# 03-VS1053B.net
KiCad netlist of a schematic drawn in Altium Designer
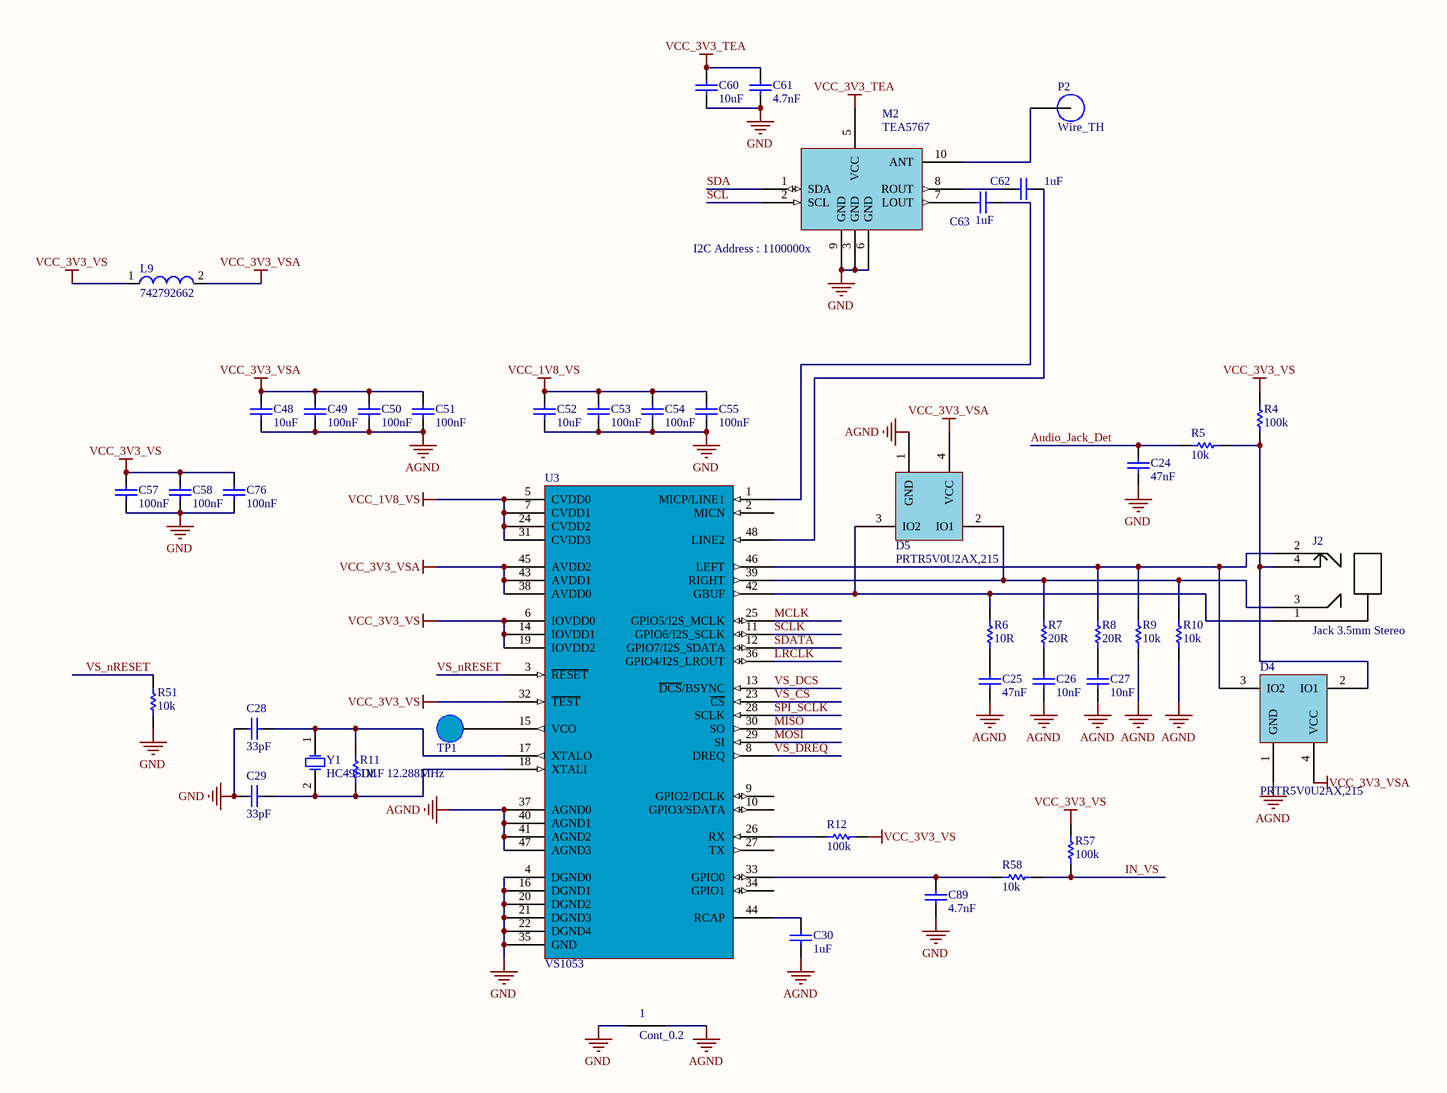
[diagram p0: 03-VS1053B.SchDoc]

(export (version "E")
  (design (tool "Eeschema 10.0.6"))
  (components
    (comp (ref "1")
      (value "Cont_0.2")
      (footprint "PcbLib:CONT_0.2")
      (description "Split Net Name 0.2mm")
      (libsource (lib "Connectors") (part "Cont_0.2"))
    )
    (comp (ref "C24")
      (value "47nF")
      (footprint "Aptustech:CAPC1608X06N")
      (description "47nF 50V 0603 X7R")
      (fields (field (name "VOLTAGE") "50V") (field (name "TOLERANCE") "10%"))
      (libsource (lib "Cap_0603") (part "47nF 50V 0603 X7R"))
    )
    (comp (ref "C25")
      (value "47nF")
      (footprint "Aptustech:CAPC1608X06N")
      (description "47nF 50V 0603 X7R")
      (fields (field (name "VOLTAGE") "50V") (field (name "TOLERANCE") "10%"))
      (libsource (lib "Cap_0603") (part "47nF 50V 0603 X7R"))
    )
    (comp (ref "C26")
      (value "10nF")
      (footprint "Aptustech:CAPC1608X06N")
      (description "10nF 50V 0603 NP0")
      (fields (field (name "VOLTAGE") "50V") (field (name "TOLERANCE") "10%"))
      (libsource (lib "Cap_0603") (part "10nF 50V 0603 NP0"))
    )
    (comp (ref "C27")
      (value "10nF")
      (footprint "Aptustech:CAPC1608X06N")
      (description "10nF 50V 0603 NP0")
      (fields (field (name "VOLTAGE") "50V") (field (name "TOLERANCE") "10%"))
      (libsource (lib "Cap_0603") (part "10nF 50V 0603 NP0"))
    )
    (comp (ref "C28")
      (value "33pF")
      (footprint "Aptustech:CAPC1608X06N")
      (description "33pF 50V 0603 NP0")
      (fields (field (name "VOLTAGE") "50V") (field (name "TOLERANCE") "10%"))
      (libsource (lib "Cap_0603") (part "33pF 50V 0603 NP0"))
    )
    (comp (ref "C29")
      (value "33pF")
      (footprint "Aptustech:CAPC1608X06N")
      (description "33pF 50V 0603 NP0")
      (fields (field (name "VOLTAGE") "50V") (field (name "TOLERANCE") "10%"))
      (libsource (lib "Cap_0603") (part "33pF 50V 0603 NP0"))
    )
    (comp (ref "C30")
      (value "1uF")
      (footprint "Aptustech:CAPC1608X06N")
      (description "1uF 16V 0603 X7R")
      (fields (field (name "VOLTAGE") "16V") (field (name "TOLERANCE") "10%"))
      (libsource (lib "Cap_0603") (part "1uF 16V 0603 X7R"))
    )
    (comp (ref "C48")
      (value "10uF")
      (footprint "Aptustech:CAPC1608X06N")
      (description "10uF 6.3V 0603 X5R")
      (fields (field (name "VOLTAGE") "6.3V") (field (name "TOLERANCE") "10%"))
      (libsource (lib "Cap_0603") (part "10uF 6.3V 0603 X5R"))
    )
    (comp (ref "C49")
      (value "100nF")
      (footprint "Aptustech:CAPC1608X06N")
      (description "100nF 25V 0603 X5R")
      (fields (field (name "VOLTAGE") "25V") (field (name "TOLERANCE") "10%"))
      (libsource (lib "Cap_0603") (part "100nF 25V 0603 X5R"))
    )
    (comp (ref "C50")
      (value "100nF")
      (footprint "Aptustech:CAPC1608X06N")
      (description "100nF 25V 0603 X5R")
      (fields (field (name "VOLTAGE") "25V") (field (name "TOLERANCE") "10%"))
      (libsource (lib "Cap_0603") (part "100nF 25V 0603 X5R"))
    )
    (comp (ref "C51")
      (value "100nF")
      (footprint "Aptustech:CAPC1608X06N")
      (description "100nF 25V 0603 X5R")
      (fields (field (name "VOLTAGE") "25V") (field (name "TOLERANCE") "10%"))
      (libsource (lib "Cap_0603") (part "100nF 25V 0603 X5R"))
    )
    (comp (ref "C52")
      (value "10uF")
      (footprint "Aptustech:CAPC1608X06N")
      (description "10uF 6.3V 0603 X5R")
      (fields (field (name "VOLTAGE") "6.3V") (field (name "TOLERANCE") "10%"))
      (libsource (lib "Cap_0603") (part "10uF 6.3V 0603 X5R"))
    )
    (comp (ref "C53")
      (value "100nF")
      (footprint "Aptustech:CAPC1608X06N")
      (description "100nF 25V 0603 X5R")
      (fields (field (name "VOLTAGE") "25V") (field (name "TOLERANCE") "10%"))
      (libsource (lib "Cap_0603") (part "100nF 25V 0603 X5R"))
    )
    (comp (ref "C54")
      (value "100nF")
      (footprint "Aptustech:CAPC1608X06N")
      (description "100nF 25V 0603 X5R")
      (fields (field (name "VOLTAGE") "25V") (field (name "TOLERANCE") "10%"))
      (libsource (lib "Cap_0603") (part "100nF 25V 0603 X5R"))
    )
    (comp (ref "C55")
      (value "100nF")
      (footprint "Aptustech:CAPC1608X06N")
      (description "100nF 25V 0603 X5R")
      (fields (field (name "VOLTAGE") "25V") (field (name "TOLERANCE") "10%"))
      (libsource (lib "Cap_0603") (part "100nF 25V 0603 X5R"))
    )
    (comp (ref "C57")
      (value "100nF")
      (footprint "Aptustech:CAPC1608X06N")
      (description "100nF 25V 0603 X5R")
      (fields (field (name "VOLTAGE") "25V") (field (name "TOLERANCE") "10%"))
      (libsource (lib "Cap_0603") (part "100nF 25V 0603 X5R"))
    )
    (comp (ref "C58")
      (value "100nF")
      (footprint "Aptustech:CAPC1608X06N")
      (description "100nF 25V 0603 X5R")
      (fields (field (name "VOLTAGE") "25V") (field (name "TOLERANCE") "10%"))
      (libsource (lib "Cap_0603") (part "100nF 25V 0603 X5R"))
    )
    (comp (ref "C60")
      (value "10uF")
      (footprint "Aptustech:CAPC1608X06N")
      (description "10uF 6.3V 0603 X5R")
      (fields (field (name "VOLTAGE") "6.3V") (field (name "TOLERANCE") "10%"))
      (libsource (lib "Cap_0603") (part "10uF 6.3V 0603 X5R"))
    )
    (comp (ref "C61")
      (value "4.7nF")
      (footprint "Aptustech:CAPC1608X06N")
      (description "4.7nF 50V 0603 X7R")
      (fields (field (name "VOLTAGE") "50V") (field (name "TOLERANCE") "10%"))
      (libsource (lib "Cap_0603") (part "4.7nF 50V 0603 X7R"))
    )
    (comp (ref "C62")
      (value "1uF")
      (footprint "Aptustech:CAPC1608X06N")
      (description "1uF 16V 0603 X7R")
      (fields (field (name "VOLTAGE") "16V") (field (name "TOLERANCE") "10%"))
      (libsource (lib "Cap_0603") (part "1uF 16V 0603 X7R"))
    )
    (comp (ref "C63")
      (value "1uF")
      (footprint "Aptustech:CAPC1608X06N")
      (description "1uF 16V 0603 X7R")
      (fields (field (name "VOLTAGE") "16V") (field (name "TOLERANCE") "10%"))
      (libsource (lib "Cap_0603") (part "1uF 16V 0603 X7R"))
    )
    (comp (ref "C76")
      (value "100nF")
      (footprint "Aptustech:CAPC1608X06N")
      (description "100nF 25V 0603 X5R")
      (fields (field (name "VOLTAGE") "25V") (field (name "TOLERANCE") "10%"))
      (libsource (lib "Cap_0603") (part "100nF 25V 0603 X5R"))
    )
    (comp (ref "C89")
      (value "4.7nF")
      (footprint "Aptustech:CAPC1608X06N")
      (description "4.7nF 50V 0603 X7R")
      (fields (field (name "VOLTAGE") "50V") (field (name "TOLERANCE") "10%"))
      (libsource (lib "Cap_0603") (part "4.7nF 50V 0603 X7R"))
    )
    (comp (ref "D4")
      (value "PRTR5V0U2AX,215")
      (footprint "Aptustech:SOT190P230X120-4N")
      (description "Ultra low capacitance double rail-to-rail ESD protection diode")
      (fields (field (name "MANUFACTURER") "Nexperia"))
      (libsource (lib "Diodes") (part "PRTR5V0U2AX,215"))
    )
    (comp (ref "D5")
      (value "PRTR5V0U2AX,215")
      (footprint "Aptustech:SOT190P230X120-4N")
      (description "Ultra low capacitance double rail-to-rail ESD protection diode")
      (fields (field (name "MANUFACTURER") "Nexperia"))
      (libsource (lib "") (part "PRTR5V0U2AX,215_1"))
    )
    (comp (ref "J2")
      (value "Jack 3.5mm Stereo")
      (footprint "Aptustech:SJ1-352xng")
      (description "SJ1-3524NG Jack 3.5mm Stereo")
      (fields (field (name "PARTNUMBER") "SJ1-3524NG") (field (name "MANUFACTURER") "CUI"))
      (libsource (lib "Connectors") (part "SJ1-3524NG"))
    )
    (comp (ref "L9")
      (value "742792662")
      (footprint "PcbLib:CAPC0603(1608)")
      (description "SMD EMI Suppression Ferrite Bead WE-CBF, Z = 1000 Ohm")
      (fields (field (name "MANUFACTURER") "Wurth"))
      (libsource (lib "Altium Content Vault") (part "CMP-0220-00178-1"))
    )
    (comp (ref "M2")
      (value "TEA5767")
      (footprint "Aptustech:MOD_TEA5767")
      (description "FM Receiver 11x11mm TEA5767")
      (fields (field (name "PARTNUMBER") "MODULE_TEA5767"))
      (libsource (lib "Modules") (part "TEA5767"))
    )
    (comp (ref "P2")
      (value "Wire_TH")
      (footprint "Aptustech:TH_0.8mm")
      (description "0.8mm Hole")
      (libsource (lib "Connectors") (part "Wire_TH"))
    )
    (comp (ref "R4")
      (value "100k")
      (footprint "Aptustech:RESC1608X06N")
      (description "Resistor 100k 0603 1%")
      (fields (field (name "TOLERANCE") "1%") (field (name "Comment") "100k_0603"))
      (libsource (lib "Res_0603") (part "100k"))
    )
    (comp (ref "R5")
      (value "10k")
      (footprint "Aptustech:RESC1608X06N")
      (description "Resistor 10k 0603 1%")
      (fields (field (name "TOLERANCE") "1%") (field (name "Comment") "10k_0603"))
      (libsource (lib "Res_0603") (part "10k"))
    )
    (comp (ref "R6")
      (value "10R")
      (footprint "Aptustech:RESC1608X06N")
      (description "Resistor 10R 0603 1%")
      (fields (field (name "TOLERANCE") "1%") (field (name "Comment") "10R_0603"))
      (libsource (lib "Res_0603") (part "10R"))
    )
    (comp (ref "R7")
      (value "20R")
      (footprint "Aptustech:RESC1608X06N")
      (description "Resistor 20R 0603 1%")
      (fields (field (name "TOLERANCE") "1%") (field (name "Comment") "20R_0603"))
      (libsource (lib "Res_0603") (part "20R"))
    )
    (comp (ref "R8")
      (value "20R")
      (footprint "Aptustech:RESC1608X06N")
      (description "Resistor 20R 0603 1%")
      (fields (field (name "TOLERANCE") "1%") (field (name "Comment") "20R_0603"))
      (libsource (lib "Res_0603") (part "20R"))
    )
    (comp (ref "R9")
      (value "10k")
      (footprint "Aptustech:RESC1608X06N")
      (description "Resistor 10k 0603 1%")
      (fields (field (name "TOLERANCE") "1%") (field (name "Comment") "10k_0603"))
      (libsource (lib "Res_0603") (part "10k"))
    )
    (comp (ref "R10")
      (value "10k")
      (footprint "Aptustech:RESC1608X06N")
      (description "Resistor 10k 0603 1%")
      (fields (field (name "TOLERANCE") "1%") (field (name "Comment") "10k_0603"))
      (libsource (lib "Res_0603") (part "10k"))
    )
    (comp (ref "R11")
      (value "1M")
      (footprint "Aptustech:RESC1608X06N")
      (description "Resistor 1M 0603 1%")
      (fields (field (name "TOLERANCE") "1%") (field (name "Comment") "1M_0603"))
      (libsource (lib "Res_0603") (part "1M"))
    )
    (comp (ref "R12")
      (value "100k")
      (footprint "Aptustech:RESC1608X06N")
      (description "Resistor 100k 0603 1%")
      (fields (field (name "TOLERANCE") "1%") (field (name "Comment") "100k_0603"))
      (libsource (lib "Res_0603") (part "100k"))
    )
    (comp (ref "R51")
      (value "10k")
      (footprint "Aptustech:RESC1608X06N")
      (description "Resistor 10k 0603 1%")
      (fields (field (name "TOLERANCE") "1%") (field (name "Comment") "10k_0603"))
      (libsource (lib "Res_0603") (part "10k"))
    )
    (comp (ref "R57")
      (value "100k")
      (footprint "Aptustech:RESC1608X06N")
      (description "Resistor 100k 0603 1%")
      (fields (field (name "TOLERANCE") "1%") (field (name "Comment") "100k_0603"))
      (libsource (lib "Res_0603") (part "100k"))
    )
    (comp (ref "R58")
      (value "10k")
      (footprint "Aptustech:RESC1608X06N")
      (description "Resistor 10k 0603 1%")
      (fields (field (name "TOLERANCE") "1%") (field (name "Comment") "10k_0603"))
      (libsource (lib "Res_0603") (part "10k"))
    )
    (comp (ref "TP1")
      (value "TP_1mm")
      (footprint "Aptustech:TP_1mm")
      (description "Test point 1mm round SMD")
      (libsource (lib "Mech") (part "TP_1mm"))
    )
    (comp (ref "U3")
      (value "VS1053")
      (footprint "Aptustech:TSQFP50P900X900X160-48N")
      (description "VS1053 DSP")
      (fields (field (name "PARTNUMBER") "VS1053b") (field (name "MANUFACTURER") "VLSI"))
      (libsource (lib "Audio") (part "VS1053"))
    )
    (comp (ref "Y1")
      (value "HC49SDLF 12.288MHz")
      (footprint "Aptustech:TXC 9C")
      (description "12.2880MHz Crystal HC49 SMT 50ppm")
      (fields (field (name "PARTNUMBER") "FOXSDLF/128-20") (field (name "MANUFACTURER") "Fox Electronic"))
      (libsource (lib "Crystal_OSC") (part "HC49SDLF 12.288MHz"))
    )
  )
  (nets
    (net (code "1") (name "/Audio_Jack_Det") (class "Default")
      (node (ref "C24") (pin "2") (pinfunction "2_2") (pintype "passive"))
      (node (ref "R5") (pin "1") (pinfunction "1_1") (pintype "passive"))
    )
    (net (code "2") (name "/IN_VS") (class "Default")
      (node (ref "R57") (pin "1") (pinfunction "1_1") (pintype "passive"))
      (node (ref "R58") (pin "1") (pinfunction "1_1") (pintype "passive"))
    )
    (net (code "3") (name "/LRCLK") (class "Default")
      (node (ref "U3") (pin "36") (pinfunction "GPIO4/I2S_LROUT_36") (pintype "bidirectional"))
    )
    (net (code "4") (name "/MCLK") (class "Default")
      (node (ref "U3") (pin "25") (pinfunction "GPIO5/I2S_MCLK_25") (pintype "bidirectional"))
    )
    (net (code "5") (name "/MISO") (class "Default")
      (node (ref "U3") (pin "30") (pinfunction "SO_30") (pintype "output"))
    )
    (net (code "6") (name "/MOSI") (class "Default")
      (node (ref "U3") (pin "29") (pinfunction "SI_29") (pintype "input"))
    )
    (net (code "7") (name "/SCL") (class "Default")
      (node (ref "M2") (pin "2") (pinfunction "SCL_2") (pintype "input"))
    )
    (net (code "8") (name "/SCLK") (class "Default")
      (node (ref "U3") (pin "11") (pinfunction "GPIO6/I2S_SCLK_11") (pintype "bidirectional"))
    )
    (net (code "9") (name "/SDA") (class "Default")
      (node (ref "M2") (pin "1") (pinfunction "SDA_1") (pintype "bidirectional"))
    )
    (net (code "10") (name "/SDATA") (class "Default")
      (node (ref "U3") (pin "12") (pinfunction "GPIO7/I2S_SDATA_12") (pintype "bidirectional"))
    )
    (net (code "11") (name "/SPI_SCLK") (class "Default")
      (node (ref "U3") (pin "28") (pinfunction "SCLK_28") (pintype "input"))
    )
    (net (code "12") (name "/VS_CS") (class "Default")
      (node (ref "U3") (pin "23") (pinfunction "~{CS}_23") (pintype "input"))
    )
    (net (code "13") (name "/VS_DCS") (class "Default")
      (node (ref "U3") (pin "13") (pinfunction "~{DCS}/BSYNC_13") (pintype "input"))
    )
    (net (code "14") (name "/VS_DREQ") (class "Default")
      (node (ref "U3") (pin "8") (pinfunction "DREQ_8") (pintype "output"))
    )
    (net (code "15") (name "/VS_nRESET") (class "Default")
      (node (ref "R51") (pin "2") (pinfunction "2_2") (pintype "passive"))
      (node (ref "U3") (pin "3") (pinfunction "~{RESET}_3") (pintype "input"))
    )
    (net (code "16") (name "AGND") (class "Default")
      (node (ref "1") (pin "2") (pintype "passive"))
      (node (ref "C25") (pin "1") (pinfunction "1_1") (pintype "passive"))
      (node (ref "C26") (pin "1") (pinfunction "1_1") (pintype "passive"))
      (node (ref "C27") (pin "1") (pinfunction "1_1") (pintype "passive"))
      (node (ref "C30") (pin "1") (pinfunction "1_1") (pintype "passive"))
      (node (ref "C48") (pin "1") (pinfunction "1_1") (pintype "passive"))
      (node (ref "C49") (pin "1") (pinfunction "1_1") (pintype "passive"))
      (node (ref "C50") (pin "1") (pinfunction "1_1") (pintype "passive"))
      (node (ref "C51") (pin "1") (pinfunction "1_1") (pintype "passive"))
      (node (ref "D4") (pin "1") (pinfunction "GND_1") (pintype "power_in"))
      (node (ref "D5") (pin "1") (pinfunction "GND_1") (pintype "power_in"))
      (node (ref "R10") (pin "2") (pinfunction "2_2") (pintype "passive"))
      (node (ref "R9") (pin "2") (pinfunction "2_2") (pintype "passive"))
      (node (ref "U3") (pin "37") (pinfunction "AGND0_37") (pintype "power_in"))
      (node (ref "U3") (pin "40") (pinfunction "AGND1_40") (pintype "power_in"))
      (node (ref "U3") (pin "41") (pinfunction "AGND2_41") (pintype "power_in"))
      (node (ref "U3") (pin "47") (pinfunction "AGND3_47") (pintype "power_in"))
    )
    (net (code "17") (name "GND") (class "Default")
      (node (ref "1") (pin "1") (pintype "passive"))
      (node (ref "C24") (pin "1") (pinfunction "1_1") (pintype "passive"))
      (node (ref "C28") (pin "1") (pinfunction "1_1") (pintype "passive"))
      (node (ref "C29") (pin "1") (pinfunction "1_1") (pintype "passive"))
      (node (ref "C52") (pin "1") (pinfunction "1_1") (pintype "passive"))
      (node (ref "C53") (pin "1") (pinfunction "1_1") (pintype "passive"))
      (node (ref "C54") (pin "1") (pinfunction "1_1") (pintype "passive"))
      (node (ref "C55") (pin "1") (pinfunction "1_1") (pintype "passive"))
      (node (ref "C57") (pin "1") (pinfunction "1_1") (pintype "passive"))
      (node (ref "C58") (pin "1") (pinfunction "1_1") (pintype "passive"))
      (node (ref "C60") (pin "1") (pinfunction "1_1") (pintype "passive"))
      (node (ref "C61") (pin "1") (pinfunction "1_1") (pintype "passive"))
      (node (ref "C76") (pin "1") (pinfunction "1_1") (pintype "passive"))
      (node (ref "C89") (pin "1") (pinfunction "1_1") (pintype "passive"))
      (node (ref "M2") (pin "3") (pinfunction "GND_3") (pintype "power_in"))
      (node (ref "M2") (pin "6") (pinfunction "GND_6") (pintype "power_in"))
      (node (ref "M2") (pin "9") (pinfunction "GND_9") (pintype "power_in"))
      (node (ref "R51") (pin "1") (pinfunction "1_1") (pintype "passive"))
      (node (ref "U3") (pin "16") (pinfunction "DGND1_16") (pintype "power_in"))
      (node (ref "U3") (pin "20") (pinfunction "DGND2_20") (pintype "power_in"))
      (node (ref "U3") (pin "21") (pinfunction "DGND3_21") (pintype "power_in"))
      (node (ref "U3") (pin "22") (pinfunction "DGND4_22") (pintype "power_in"))
      (node (ref "U3") (pin "35") (pinfunction "GND_35") (pintype "power_in"))
      (node (ref "U3") (pin "4") (pinfunction "DGND0_4") (pintype "power_in"))
    )
    (net (code "18") (name "Net-(C25-Pad2)") (class "Default")
      (node (ref "C25") (pin "2") (pinfunction "2_2") (pintype "passive"))
      (node (ref "R6") (pin "1") (pinfunction "1_1") (pintype "passive"))
    )
    (net (code "19") (name "Net-(C26-Pad2)") (class "Default")
      (node (ref "C26") (pin "2") (pinfunction "2_2") (pintype "passive"))
      (node (ref "R7") (pin "1") (pinfunction "1_1") (pintype "passive"))
    )
    (net (code "20") (name "Net-(C27-Pad2)") (class "Default")
      (node (ref "C27") (pin "2") (pinfunction "2_2") (pintype "passive"))
      (node (ref "R8") (pin "1") (pinfunction "1_1") (pintype "passive"))
    )
    (net (code "21") (name "Net-(D4-IO1)") (class "Default")
      (node (ref "D4") (pin "2") (pinfunction "IO1_2") (pintype "passive"))
      (node (ref "J2") (pin "4") (pinfunction "4_4") (pintype "passive"))
      (node (ref "R4") (pin "1") (pinfunction "1_1") (pintype "passive"))
      (node (ref "R5") (pin "2") (pinfunction "2_2") (pintype "passive"))
    )
    (net (code "22") (name "Net-(D4-IO2)") (class "Default")
      (node (ref "D4") (pin "3") (pinfunction "IO2_3") (pintype "passive"))
      (node (ref "J2") (pin "2") (pinfunction "2_2") (pintype "passive"))
      (node (ref "R8") (pin "2") (pinfunction "2_2") (pintype "passive"))
      (node (ref "R9") (pin "1") (pinfunction "1_1") (pintype "passive"))
      (node (ref "U3") (pin "46") (pinfunction "LEFT_46") (pintype "output"))
    )
    (net (code "23") (name "Net-(D5-IO1)") (class "Default")
      (node (ref "D5") (pin "2") (pinfunction "IO1_2") (pintype "passive"))
      (node (ref "J2") (pin "3") (pinfunction "3_3") (pintype "passive"))
      (node (ref "R10") (pin "1") (pinfunction "1_1") (pintype "passive"))
      (node (ref "R7") (pin "2") (pinfunction "2_2") (pintype "passive"))
      (node (ref "U3") (pin "39") (pinfunction "RIGHT_39") (pintype "output"))
    )
    (net (code "24") (name "Net-(D5-IO2)") (class "Default")
      (node (ref "D5") (pin "3") (pinfunction "IO2_3") (pintype "passive"))
      (node (ref "J2") (pin "1") (pinfunction "1_1") (pintype "passive"))
      (node (ref "R6") (pin "2") (pinfunction "2_2") (pintype "passive"))
      (node (ref "U3") (pin "42") (pinfunction "GBUF_42") (pintype "output"))
    )
    (net (code "25") (name "Net-(M2-ANT)") (class "Default")
      (node (ref "M2") (pin "10") (pinfunction "ANT_10") (pintype "passive"))
      (node (ref "P2") (pin "1") (pinfunction "1_1") (pintype "passive"))
    )
    (net (code "26") (name "Net-(M2-LOUT)") (class "Default")
      (node (ref "C63") (pin "1") (pinfunction "1_1") (pintype "passive"))
      (node (ref "M2") (pin "7") (pinfunction "LOUT_7") (pintype "output"))
    )
    (net (code "27") (name "Net-(M2-ROUT)") (class "Default")
      (node (ref "C62") (pin "1") (pinfunction "1_1") (pintype "passive"))
      (node (ref "M2") (pin "8") (pinfunction "ROUT_8") (pintype "output"))
    )
    (net (code "28") (name "Net-(U3-GPIO0)") (class "Default")
      (node (ref "C89") (pin "2") (pinfunction "2_2") (pintype "passive"))
      (node (ref "R58") (pin "2") (pinfunction "2_2") (pintype "passive"))
      (node (ref "U3") (pin "33") (pinfunction "GPIO0_33") (pintype "bidirectional"))
    )
    (net (code "29") (name "Net-(U3-LINE2)") (class "Default")
      (node (ref "C62") (pin "2") (pinfunction "2_2") (pintype "passive"))
      (node (ref "U3") (pin "48") (pinfunction "LINE2_48") (pintype "input"))
    )
    (net (code "30") (name "Net-(U3-MICP{slash}LINE1)") (class "Default")
      (node (ref "C63") (pin "2") (pinfunction "2_2") (pintype "passive"))
      (node (ref "U3") (pin "1") (pinfunction "MICP/LINE1_1") (pintype "input"))
    )
    (net (code "31") (name "Net-(U3-RCAP)") (class "Default")
      (node (ref "C30") (pin "2") (pinfunction "2_2") (pintype "passive"))
      (node (ref "U3") (pin "44") (pinfunction "RCAP_44") (pintype "passive"))
    )
    (net (code "32") (name "Net-(U3-RX)") (class "Default")
      (node (ref "R12") (pin "1") (pinfunction "1_1") (pintype "passive"))
      (node (ref "U3") (pin "26") (pinfunction "RX_26") (pintype "input"))
    )
    (net (code "33") (name "Net-(U3-VCO)") (class "Default")
      (node (ref "TP1") (pin "1") (pinfunction "1_1") (pintype "passive"))
      (node (ref "U3") (pin "15") (pinfunction "VCO_15") (pintype "output"))
    )
    (net (code "34") (name "Net-(U3-XTALI)") (class "Default")
      (node (ref "C29") (pin "2") (pinfunction "2_2") (pintype "passive"))
      (node (ref "R11") (pin "1") (pinfunction "1_1") (pintype "passive"))
      (node (ref "U3") (pin "18") (pinfunction "XTALI_18") (pintype "input"))
      (node (ref "Y1") (pin "2") (pinfunction "OSC2_2") (pintype "passive"))
    )
    (net (code "35") (name "Net-(U3-XTALO)") (class "Default")
      (node (ref "C28") (pin "2") (pinfunction "2_2") (pintype "passive"))
      (node (ref "R11") (pin "2") (pinfunction "2_2") (pintype "passive"))
      (node (ref "U3") (pin "17") (pinfunction "XTALO_17") (pintype "output"))
      (node (ref "Y1") (pin "1") (pinfunction "OSC1_1") (pintype "passive"))
    )
    (net (code "36") (name "VCC_1V8_VS") (class "Default")
      (node (ref "C52") (pin "2") (pinfunction "2_2") (pintype "passive"))
      (node (ref "C53") (pin "2") (pinfunction "2_2") (pintype "passive"))
      (node (ref "C54") (pin "2") (pinfunction "2_2") (pintype "passive"))
      (node (ref "C55") (pin "2") (pinfunction "2_2") (pintype "passive"))
      (node (ref "U3") (pin "24") (pinfunction "CVDD2_24") (pintype "power_in"))
      (node (ref "U3") (pin "31") (pinfunction "CVDD3_31") (pintype "power_in"))
      (node (ref "U3") (pin "5") (pinfunction "CVDD0_5") (pintype "power_in"))
      (node (ref "U3") (pin "7") (pinfunction "CVDD1_7") (pintype "power_in"))
    )
    (net (code "37") (name "VCC_3V3_TEA") (class "Default")
      (node (ref "C60") (pin "2") (pinfunction "2_2") (pintype "passive"))
      (node (ref "C61") (pin "2") (pinfunction "2_2") (pintype "passive"))
      (node (ref "M2") (pin "5") (pinfunction "VCC_5") (pintype "power_in"))
    )
    (net (code "38") (name "VCC_3V3_VS") (class "Default")
      (node (ref "C57") (pin "2") (pinfunction "2_2") (pintype "passive"))
      (node (ref "C58") (pin "2") (pinfunction "2_2") (pintype "passive"))
      (node (ref "C76") (pin "2") (pinfunction "2_2") (pintype "passive"))
      (node (ref "L9") (pin "1") (pinfunction "1_1") (pintype "passive"))
      (node (ref "R12") (pin "2") (pinfunction "2_2") (pintype "passive"))
      (node (ref "R4") (pin "2") (pinfunction "2_2") (pintype "passive"))
      (node (ref "R57") (pin "2") (pinfunction "2_2") (pintype "passive"))
      (node (ref "U3") (pin "14") (pinfunction "IOVDD1_14") (pintype "passive"))
      (node (ref "U3") (pin "19") (pinfunction "IOVDD2_19") (pintype "passive"))
      (node (ref "U3") (pin "32") (pinfunction "~{TEST}_32") (pintype "input"))
      (node (ref "U3") (pin "6") (pinfunction "IOVDD0_6") (pintype "passive"))
    )
    (net (code "39") (name "VCC_3V3_VSA") (class "Default")
      (node (ref "C48") (pin "2") (pinfunction "2_2") (pintype "passive"))
      (node (ref "C49") (pin "2") (pinfunction "2_2") (pintype "passive"))
      (node (ref "C50") (pin "2") (pinfunction "2_2") (pintype "passive"))
      (node (ref "C51") (pin "2") (pinfunction "2_2") (pintype "passive"))
      (node (ref "D4") (pin "4") (pinfunction "VCC_4") (pintype "power_in"))
      (node (ref "D5") (pin "4") (pinfunction "VCC_4") (pintype "power_in"))
      (node (ref "L9") (pin "2") (pinfunction "2_2") (pintype "passive"))
      (node (ref "U3") (pin "38") (pinfunction "AVDD0_38") (pintype "power_in"))
      (node (ref "U3") (pin "43") (pinfunction "AVDD1_43") (pintype "power_in"))
      (node (ref "U3") (pin "45") (pinfunction "AVDD2_45") (pintype "power_in"))
    )
    (net (code "40") (name "unconnected-(U3-GPIO1-Pad34)") (class "Default")
      (node (ref "U3") (pin "34") (pinfunction "GPIO1_34") (pintype "bidirectional"))
    )
    (net (code "41") (name "unconnected-(U3-GPIO2{slash}DCLK-Pad9)") (class "Default")
      (node (ref "U3") (pin "9") (pinfunction "GPIO2/DCLK_9") (pintype "bidirectional"))
    )
    (net (code "42") (name "unconnected-(U3-GPIO3{slash}SDATA-Pad10)") (class "Default")
      (node (ref "U3") (pin "10") (pinfunction "GPIO3/SDATA_10") (pintype "bidirectional"))
    )
    (net (code "43") (name "unconnected-(U3-MICN-Pad2)") (class "Default")
      (node (ref "U3") (pin "2") (pinfunction "MICN_2") (pintype "input"))
    )
    (net (code "44") (name "unconnected-(U3-TX-Pad27)") (class "Default")
      (node (ref "U3") (pin "27") (pinfunction "TX_27") (pintype "output"))
    )
  )
)
